# Bus_Isolator.net
KiCad netlist of a schematic drawn in EAGLE
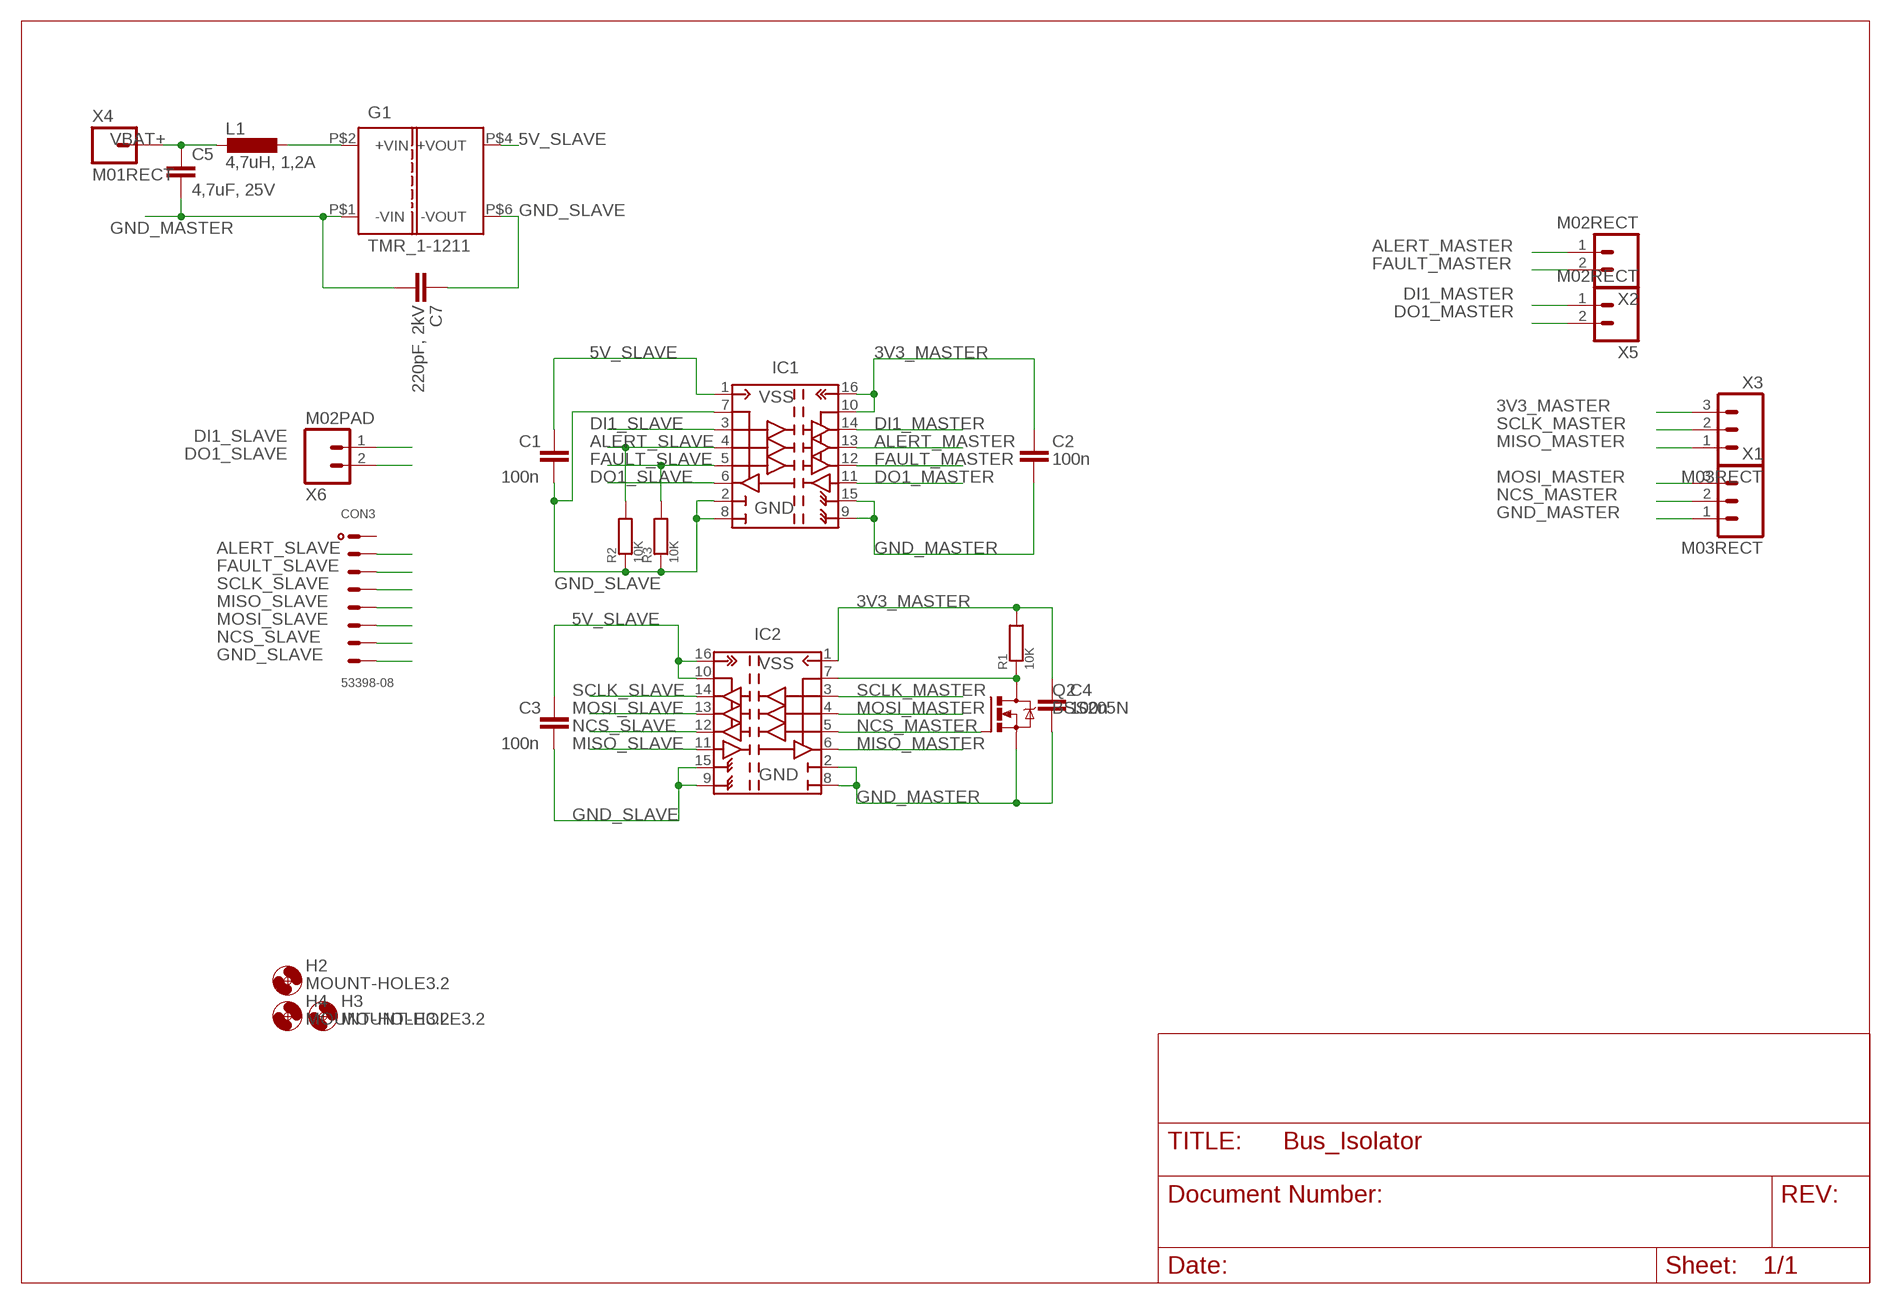
[diagram p0: schematic, sheet 1]

(export (version "E")
  (design (tool "Eeschema 10.0.6"))
  (components
    (comp (ref "C1")
      (value "100n")
      (footprint "eagle-import:C0805")
      (libsource (lib "eagle-import") (part "CSTD"))
    )
    (comp (ref "C2")
      (value "100n")
      (footprint "eagle-import:C0805")
      (libsource (lib "eagle-import") (part "CSTD"))
    )
    (comp (ref "C3")
      (value "100n")
      (footprint "eagle-import:C0805")
      (libsource (lib "eagle-import") (part "CSTD"))
    )
    (comp (ref "C4")
      (value "100n")
      (footprint "eagle-import:C0805")
      (libsource (lib "eagle-import") (part "CSTD"))
    )
    (comp (ref "C5")
      (value "4,7uF, 25V")
      (footprint "eagle-import:C0805")
      (libsource (lib "eagle-import") (part "C-EUC0805"))
    )
    (comp (ref "C7")
      (value "220pF, 2kV")
      (footprint "eagle-import:C1210_HV")
      (libsource (lib "eagle-import") (part "CC1210_HV"))
    )
    (comp (ref "CON3")
      (value "53398-08")
      (footprint "eagle-import:53398-08")
      (libsource (lib "eagle-import") (part "53?-08398"))
    )
    (comp (ref "G1")
      (value "TMR_1-1211")
      (footprint "eagle-import:TMR_1-__1_")
      (libsource (lib "eagle-import") (part "TMR_1-??1?"))
    )
    (comp (ref "H2")
      (value "MOUNT-HOLE3.2")
      (footprint "eagle-import:3,2")
      (libsource (lib "eagle-import") (part "MOUNT-HOLE3.2"))
    )
    (comp (ref "H3")
      (value "MOUNT-HOLE3.2")
      (footprint "eagle-import:3,2")
      (libsource (lib "eagle-import") (part "MOUNT-HOLE3.2"))
    )
    (comp (ref "H4")
      (value "MOUNT-HOLE3.2")
      (footprint "eagle-import:3,2")
      (libsource (lib "eagle-import") (part "MOUNT-HOLE3.2"))
    )
    (comp (ref "IC1")
      (value "ISO7241")
      (footprint "eagle-import:R-PDSO-G16")
      (libsource (lib "eagle-import") (part "ISO7241"))
    )
    (comp (ref "IC2")
      (value "ISO7241")
      (footprint "eagle-import:R-PDSO-G16")
      (libsource (lib "eagle-import") (part "ISO7241"))
    )
    (comp (ref "L1")
      (value "4,7uH, 1,2A")
      (footprint "eagle-import:L3225M")
      (libsource (lib "eagle-import") (part "L-EUL3225M"))
    )
    (comp (ref "Q2")
      (value "BSS205N")
      (footprint "eagle-import:SOT23")
      (libsource (lib "eagle-import") (part "BSS205N"))
    )
    (comp (ref "R1")
      (value "10K")
      (footprint "eagle-import:R0603")
      (libsource (lib "eagle-import") (part "R0603"))
    )
    (comp (ref "R2")
      (value "10K")
      (footprint "eagle-import:R0805")
      (libsource (lib "eagle-import") (part "R"))
    )
    (comp (ref "R3")
      (value "10K")
      (footprint "eagle-import:R0805")
      (libsource (lib "eagle-import") (part "R"))
    )
    (comp (ref "X1")
      (value "M03RECT")
      (footprint "eagle-import:1X03_RECT")
      (libsource (lib "eagle-import") (part "M03RECT"))
    )
    (comp (ref "X2")
      (value "M02RECT")
      (footprint "eagle-import:1X02_RECT")
      (libsource (lib "eagle-import") (part "M02RECT"))
    )
    (comp (ref "X3")
      (value "M03RECT")
      (footprint "eagle-import:1X03_RECT")
      (libsource (lib "eagle-import") (part "M03RECT"))
    )
    (comp (ref "X4")
      (value "M01RECT")
      (footprint "eagle-import:1X01_RECT")
      (libsource (lib "eagle-import") (part "M01RECT"))
    )
    (comp (ref "X5")
      (value "M02RECT")
      (footprint "eagle-import:1X02_RECT")
      (libsource (lib "eagle-import") (part "M02RECT"))
    )
    (comp (ref "X6")
      (value "M02PAD")
      (footprint "eagle-import:1X02")
      (libsource (lib "eagle-import") (part "M02PAD"))
    )
  )
  (nets
    (net (code "1") (name "/3V3_MASTER") (class "Default")
      (node (ref "C2") (pin "2") (pinfunction "2_2") (pintype "passive"))
      (node (ref "C4") (pin "2") (pinfunction "2_2") (pintype "passive"))
      (node (ref "IC1") (pin "10") (pinfunction "EN2_10") (pintype "bidirectional"))
      (node (ref "IC1") (pin "16") (pinfunction "VCC2_16") (pintype "bidirectional"))
      (node (ref "IC2") (pin "1") (pinfunction "VCC1_1") (pintype "bidirectional"))
      (node (ref "R1") (pin "2") (pinfunction "2_2") (pintype "passive"))
      (node (ref "X3") (pin "3") (pinfunction "3_3") (pintype "passive"))
    )
    (net (code "2") (name "/5V_SLAVE") (class "Default")
      (node (ref "C1") (pin "2") (pinfunction "2_2") (pintype "passive"))
      (node (ref "C3") (pin "2") (pinfunction "2_2") (pintype "passive"))
      (node (ref "G1") (pin "P$4") (pinfunction "+VOUT_P$4") (pintype "bidirectional"))
      (node (ref "IC1") (pin "1") (pinfunction "VCC1_1") (pintype "bidirectional"))
      (node (ref "IC2") (pin "10") (pinfunction "EN2_10") (pintype "bidirectional"))
      (node (ref "IC2") (pin "16") (pinfunction "VCC2_16") (pintype "bidirectional"))
    )
    (net (code "3") (name "/ALERT_MASTER") (class "Default")
      (node (ref "IC1") (pin "13") (pinfunction "OUT_B_13") (pintype "bidirectional"))
      (node (ref "X2") (pin "1") (pinfunction "1_1") (pintype "passive"))
    )
    (net (code "4") (name "/ALERT_SLAVE") (class "Default")
      (node (ref "CON3") (pin "2") (pinfunction "2_2") (pintype "passive"))
      (node (ref "IC1") (pin "4") (pinfunction "IN_B_4") (pintype "bidirectional"))
      (node (ref "R2") (pin "2") (pinfunction "2_2") (pintype "passive"))
    )
    (net (code "5") (name "/DI1_MASTER") (class "Default")
      (node (ref "IC1") (pin "14") (pinfunction "OUT_A_14") (pintype "bidirectional"))
      (node (ref "X5") (pin "1") (pinfunction "1_1") (pintype "passive"))
    )
    (net (code "6") (name "/DI1_SLAVE") (class "Default")
      (node (ref "IC1") (pin "3") (pinfunction "IN_A_3") (pintype "bidirectional"))
      (node (ref "X6") (pin "1") (pinfunction "1_1") (pintype "passive"))
    )
    (net (code "7") (name "/DO1_MASTER") (class "Default")
      (node (ref "IC1") (pin "11") (pinfunction "IN_D_11") (pintype "bidirectional"))
      (node (ref "X5") (pin "2") (pinfunction "2_2") (pintype "passive"))
    )
    (net (code "8") (name "/DO1_SLAVE") (class "Default")
      (node (ref "IC1") (pin "6") (pinfunction "OUT_D_6") (pintype "bidirectional"))
      (node (ref "X6") (pin "2") (pinfunction "2_2") (pintype "passive"))
    )
    (net (code "9") (name "/FAULT_MASTER") (class "Default")
      (node (ref "IC1") (pin "12") (pinfunction "OUT_C_12") (pintype "bidirectional"))
      (node (ref "X2") (pin "2") (pinfunction "2_2") (pintype "passive"))
    )
    (net (code "10") (name "/FAULT_SLAVE") (class "Default")
      (node (ref "CON3") (pin "3") (pinfunction "3_3") (pintype "passive"))
      (node (ref "IC1") (pin "5") (pinfunction "IN_C_5") (pintype "bidirectional"))
      (node (ref "R3") (pin "2") (pinfunction "2_2") (pintype "passive"))
    )
    (net (code "11") (name "/GND_MASTER") (class "Default")
      (node (ref "C2") (pin "1") (pinfunction "1_1") (pintype "passive"))
      (node (ref "C4") (pin "1") (pinfunction "1_1") (pintype "passive"))
      (node (ref "C5") (pin "2") (pinfunction "2_2") (pintype "passive"))
      (node (ref "C7") (pin "P$1") (pinfunction "1_P$1") (pintype "passive"))
      (node (ref "G1") (pin "P$1") (pinfunction "-VIN_P$1") (pintype "bidirectional"))
      (node (ref "IC1") (pin "15") (pinfunction "GND21_15") (pintype "bidirectional"))
      (node (ref "IC1") (pin "9") (pinfunction "GND22_9") (pintype "bidirectional"))
      (node (ref "IC2") (pin "2") (pinfunction "GND11_2") (pintype "bidirectional"))
      (node (ref "IC2") (pin "8") (pinfunction "GND12_8") (pintype "bidirectional"))
      (node (ref "Q2") (pin "2") (pinfunction "S_2") (pintype "passive"))
      (node (ref "X1") (pin "1") (pinfunction "1_1") (pintype "passive"))
    )
    (net (code "12") (name "/GND_SLAVE") (class "Default")
      (node (ref "C1") (pin "1") (pinfunction "1_1") (pintype "passive"))
      (node (ref "C3") (pin "1") (pinfunction "1_1") (pintype "passive"))
      (node (ref "C7") (pin "P$2") (pinfunction "2_P$2") (pintype "passive"))
      (node (ref "CON3") (pin "8") (pinfunction "8_8") (pintype "passive"))
      (node (ref "G1") (pin "P$6") (pinfunction "-VOUT_P$6") (pintype "bidirectional"))
      (node (ref "IC1") (pin "2") (pinfunction "GND11_2") (pintype "bidirectional"))
      (node (ref "IC1") (pin "7") (pinfunction "EN1_7") (pintype "bidirectional"))
      (node (ref "IC1") (pin "8") (pinfunction "GND12_8") (pintype "bidirectional"))
      (node (ref "IC2") (pin "15") (pinfunction "GND21_15") (pintype "bidirectional"))
      (node (ref "IC2") (pin "9") (pinfunction "GND22_9") (pintype "bidirectional"))
      (node (ref "R2") (pin "1") (pinfunction "1_1") (pintype "passive"))
      (node (ref "R3") (pin "1") (pinfunction "1_1") (pintype "passive"))
    )
    (net (code "13") (name "/MISO_MASTER") (class "Default")
      (node (ref "IC2") (pin "6") (pinfunction "OUT_D_6") (pintype "bidirectional"))
      (node (ref "X3") (pin "1") (pinfunction "1_1") (pintype "passive"))
    )
    (net (code "14") (name "/MISO_SLAVE") (class "Default")
      (node (ref "CON3") (pin "5") (pinfunction "5_5") (pintype "passive"))
      (node (ref "IC2") (pin "11") (pinfunction "IN_D_11") (pintype "bidirectional"))
    )
    (net (code "15") (name "/MOSI_MASTER") (class "Default")
      (node (ref "IC2") (pin "4") (pinfunction "IN_B_4") (pintype "bidirectional"))
      (node (ref "X1") (pin "3") (pinfunction "3_3") (pintype "passive"))
    )
    (net (code "16") (name "/MOSI_SLAVE") (class "Default")
      (node (ref "CON3") (pin "6") (pinfunction "6_6") (pintype "passive"))
      (node (ref "IC2") (pin "13") (pinfunction "OUT_B_13") (pintype "bidirectional"))
    )
    (net (code "17") (name "/NCS_MASTER") (class "Default")
      (node (ref "IC2") (pin "5") (pinfunction "IN_C_5") (pintype "bidirectional"))
      (node (ref "Q2") (pin "1") (pinfunction "G_1") (pintype "passive"))
      (node (ref "X1") (pin "2") (pinfunction "2_2") (pintype "passive"))
    )
    (net (code "18") (name "/NCS_SLAVE") (class "Default")
      (node (ref "CON3") (pin "7") (pinfunction "7_7") (pintype "passive"))
      (node (ref "IC2") (pin "12") (pinfunction "OUT_C_12") (pintype "bidirectional"))
    )
    (net (code "19") (name "/SCLK_MASTER") (class "Default")
      (node (ref "IC2") (pin "3") (pinfunction "IN_A_3") (pintype "bidirectional"))
      (node (ref "X3") (pin "2") (pinfunction "2_2") (pintype "passive"))
    )
    (net (code "20") (name "/SCLK_SLAVE") (class "Default")
      (node (ref "CON3") (pin "4") (pinfunction "4_4") (pintype "passive"))
      (node (ref "IC2") (pin "14") (pinfunction "OUT_A_14") (pintype "bidirectional"))
    )
    (net (code "21") (name "/VBAT+") (class "Default")
      (node (ref "C5") (pin "1") (pinfunction "1_1") (pintype "passive"))
      (node (ref "L1") (pin "2") (pinfunction "2_2") (pintype "passive"))
      (node (ref "X4") (pin "1") (pinfunction "1_1") (pintype "passive"))
    )
    (net (code "22") (name "Net-(G1-+VIN)") (class "Default")
      (node (ref "G1") (pin "P$2") (pinfunction "+VIN_P$2") (pintype "bidirectional"))
      (node (ref "L1") (pin "1") (pinfunction "1_1") (pintype "passive"))
    )
    (net (code "23") (name "Net-(IC2-EN1)") (class "Default")
      (node (ref "IC2") (pin "7") (pinfunction "EN1_7") (pintype "bidirectional"))
      (node (ref "Q2") (pin "3") (pinfunction "D_3") (pintype "passive"))
      (node (ref "R1") (pin "1") (pinfunction "1_1") (pintype "passive"))
    )
    (net (code "24") (name "unconnected-(CON3-Pad1)") (class "Default")
      (node (ref "CON3") (pin "1") (pinfunction "1_1") (pintype "passive"))
    )
  )
)
